# Backplane.net
KiCad netlist of a schematic drawn in EAGLE
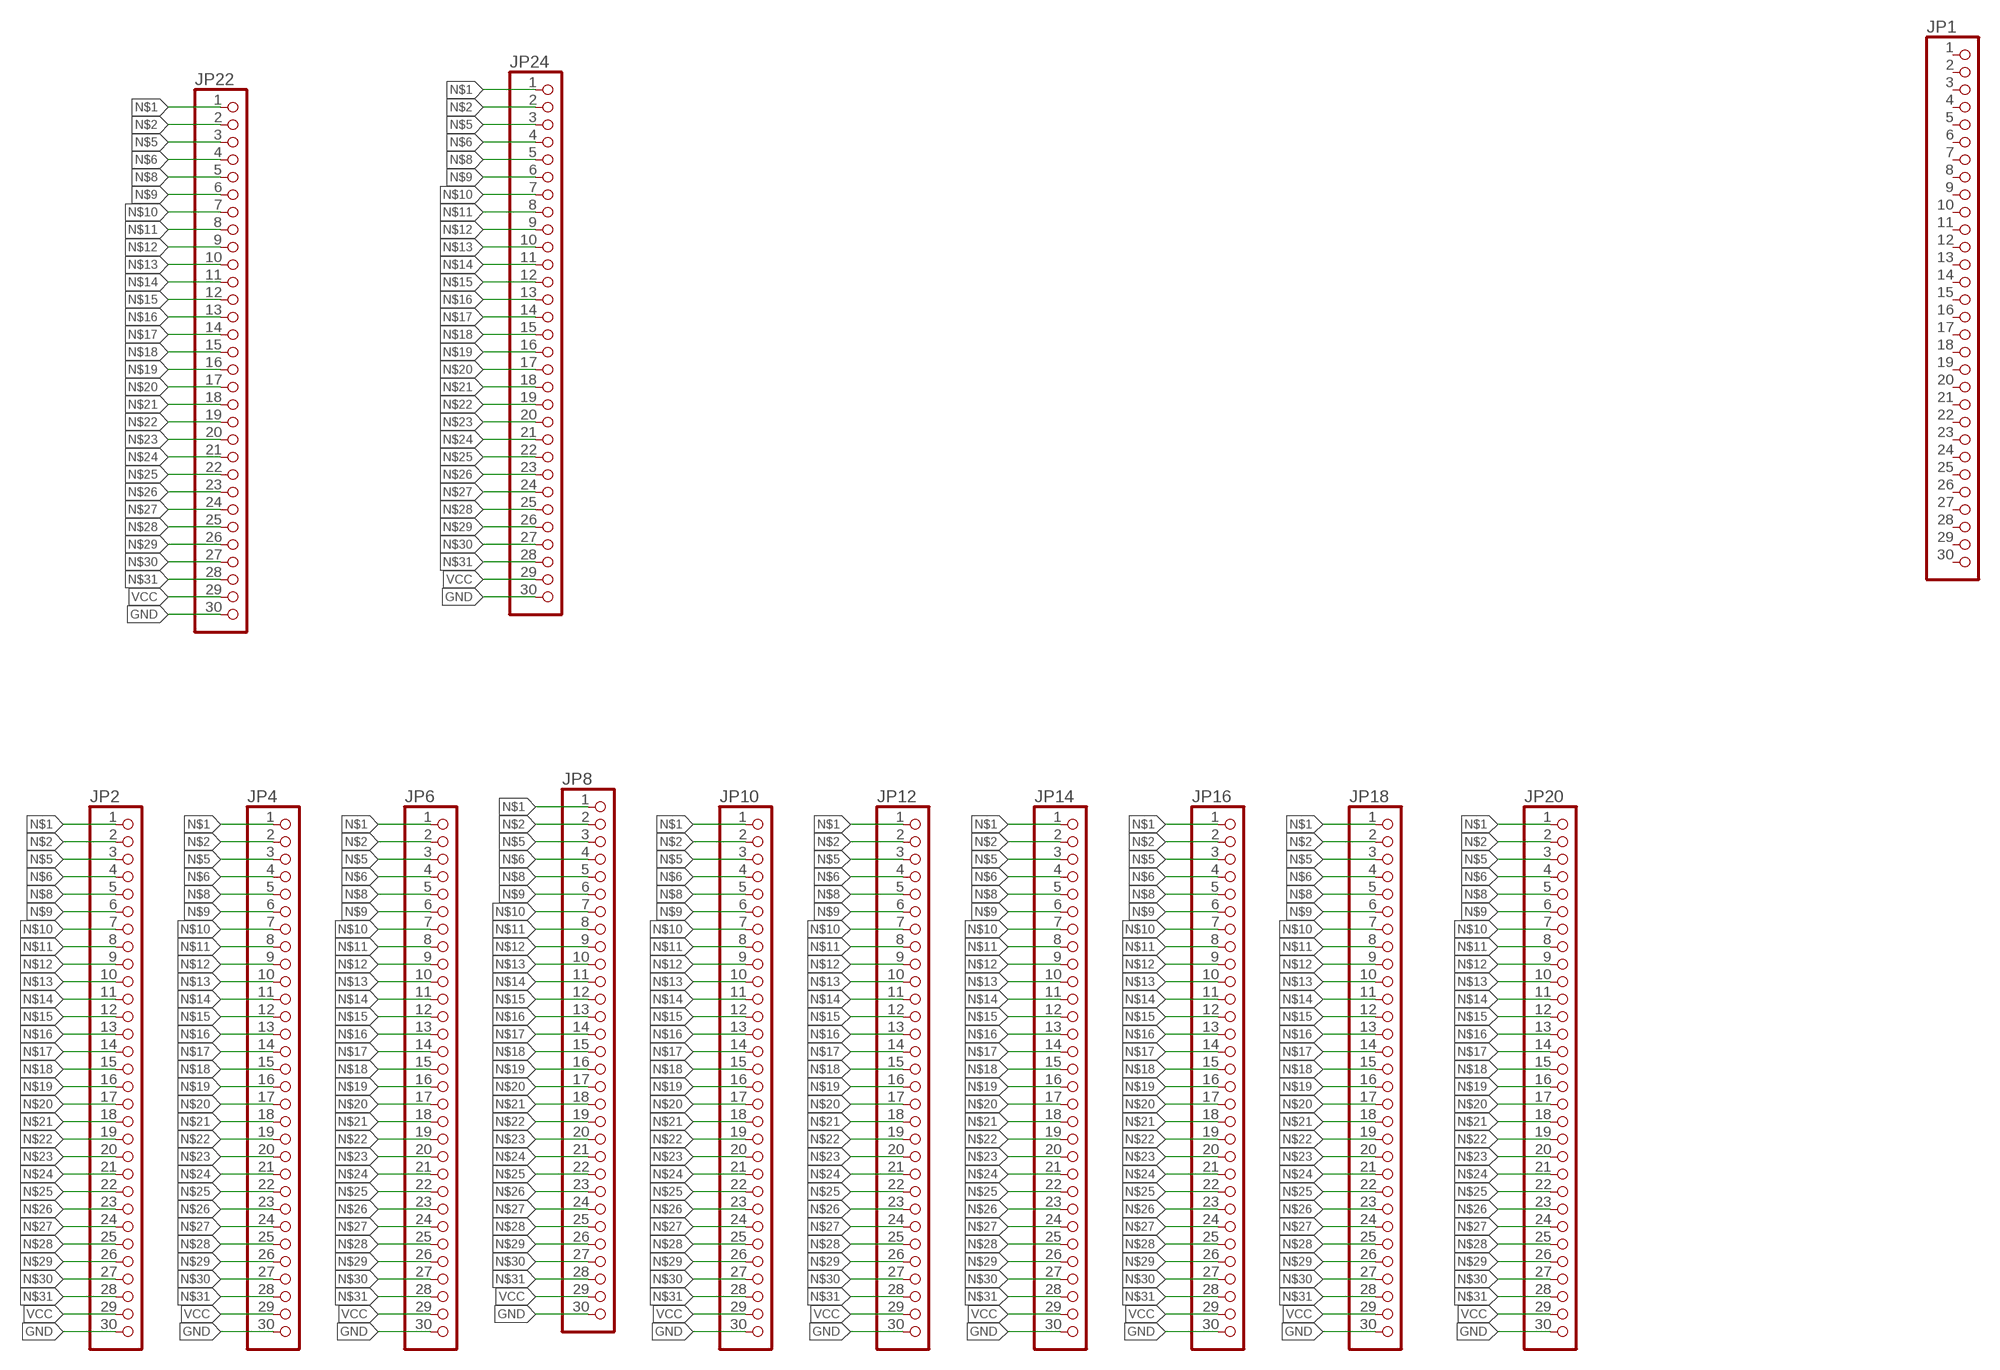
[diagram p0: schematic, sheet 1]

(export (version "E")
  (design (tool "Eeschema 10.0.6"))
  (components
    (comp (ref "JP1")
      (value "PINHD-1X30")
      (footprint "eagle-import:1X30")
      (libsource (lib "eagle-import") (part "PINHD-1X30"))
    )
    (comp (ref "JP2")
      (value "PINHD-1X30")
      (footprint "eagle-import:1X30")
      (libsource (lib "eagle-import") (part "PINHD-1X30"))
    )
    (comp (ref "JP4")
      (value "PINHD-1X30")
      (footprint "eagle-import:1X30")
      (libsource (lib "eagle-import") (part "PINHD-1X30"))
    )
    (comp (ref "JP6")
      (value "PINHD-1X30")
      (footprint "eagle-import:1X30")
      (libsource (lib "eagle-import") (part "PINHD-1X30"))
    )
    (comp (ref "JP8")
      (value "PINHD-1X30")
      (footprint "eagle-import:1X30")
      (libsource (lib "eagle-import") (part "PINHD-1X30"))
    )
    (comp (ref "JP10")
      (value "PINHD-1X30")
      (footprint "eagle-import:1X30")
      (libsource (lib "eagle-import") (part "PINHD-1X30"))
    )
    (comp (ref "JP12")
      (value "PINHD-1X30")
      (footprint "eagle-import:1X30")
      (libsource (lib "eagle-import") (part "PINHD-1X30"))
    )
    (comp (ref "JP14")
      (value "PINHD-1X30")
      (footprint "eagle-import:1X30")
      (libsource (lib "eagle-import") (part "PINHD-1X30"))
    )
    (comp (ref "JP16")
      (value "PINHD-1X30")
      (footprint "eagle-import:1X30")
      (libsource (lib "eagle-import") (part "PINHD-1X30"))
    )
    (comp (ref "JP18")
      (value "PINHD-1X30")
      (footprint "eagle-import:1X30")
      (libsource (lib "eagle-import") (part "PINHD-1X30"))
    )
    (comp (ref "JP20")
      (value "PINHD-1X30")
      (footprint "eagle-import:1X30")
      (libsource (lib "eagle-import") (part "PINHD-1X30"))
    )
    (comp (ref "JP22")
      (value "PINHD-1X30")
      (footprint "eagle-import:1X30")
      (libsource (lib "eagle-import") (part "PINHD-1X30"))
    )
    (comp (ref "JP24")
      (value "PINHD-1X30")
      (footprint "eagle-import:1X30")
      (libsource (lib "eagle-import") (part "PINHD-1X30"))
    )
  )
  (nets
    (net (code "1") (name "GND") (class "Default")
      (node (ref "JP10") (pin "30") (pinfunction "30_30") (pintype "passive"))
      (node (ref "JP12") (pin "30") (pinfunction "30_30") (pintype "passive"))
      (node (ref "JP14") (pin "30") (pinfunction "30_30") (pintype "passive"))
      (node (ref "JP16") (pin "30") (pinfunction "30_30") (pintype "passive"))
      (node (ref "JP18") (pin "30") (pinfunction "30_30") (pintype "passive"))
      (node (ref "JP2") (pin "30") (pinfunction "30_30") (pintype "passive"))
      (node (ref "JP20") (pin "30") (pinfunction "30_30") (pintype "passive"))
      (node (ref "JP22") (pin "30") (pinfunction "30_30") (pintype "passive"))
      (node (ref "JP24") (pin "30") (pinfunction "30_30") (pintype "passive"))
      (node (ref "JP4") (pin "30") (pinfunction "30_30") (pintype "passive"))
      (node (ref "JP6") (pin "30") (pinfunction "30_30") (pintype "passive"))
      (node (ref "JP8") (pin "30") (pinfunction "30_30") (pintype "passive"))
    )
    (net (code "2") (name "N$1") (class "Default")
      (node (ref "JP10") (pin "1") (pinfunction "1_1") (pintype "passive"))
      (node (ref "JP12") (pin "1") (pinfunction "1_1") (pintype "passive"))
      (node (ref "JP14") (pin "1") (pinfunction "1_1") (pintype "passive"))
      (node (ref "JP16") (pin "1") (pinfunction "1_1") (pintype "passive"))
      (node (ref "JP18") (pin "1") (pinfunction "1_1") (pintype "passive"))
      (node (ref "JP2") (pin "1") (pinfunction "1_1") (pintype "passive"))
      (node (ref "JP20") (pin "1") (pinfunction "1_1") (pintype "passive"))
      (node (ref "JP22") (pin "1") (pinfunction "1_1") (pintype "passive"))
      (node (ref "JP24") (pin "1") (pinfunction "1_1") (pintype "passive"))
      (node (ref "JP4") (pin "1") (pinfunction "1_1") (pintype "passive"))
      (node (ref "JP6") (pin "1") (pinfunction "1_1") (pintype "passive"))
      (node (ref "JP8") (pin "1") (pinfunction "1_1") (pintype "passive"))
    )
    (net (code "3") (name "N$2") (class "Default")
      (node (ref "JP10") (pin "2") (pinfunction "2_2") (pintype "passive"))
      (node (ref "JP12") (pin "2") (pinfunction "2_2") (pintype "passive"))
      (node (ref "JP14") (pin "2") (pinfunction "2_2") (pintype "passive"))
      (node (ref "JP16") (pin "2") (pinfunction "2_2") (pintype "passive"))
      (node (ref "JP18") (pin "2") (pinfunction "2_2") (pintype "passive"))
      (node (ref "JP2") (pin "2") (pinfunction "2_2") (pintype "passive"))
      (node (ref "JP20") (pin "2") (pinfunction "2_2") (pintype "passive"))
      (node (ref "JP22") (pin "2") (pinfunction "2_2") (pintype "passive"))
      (node (ref "JP24") (pin "2") (pinfunction "2_2") (pintype "passive"))
      (node (ref "JP4") (pin "2") (pinfunction "2_2") (pintype "passive"))
      (node (ref "JP6") (pin "2") (pinfunction "2_2") (pintype "passive"))
      (node (ref "JP8") (pin "2") (pinfunction "2_2") (pintype "passive"))
    )
    (net (code "4") (name "N$5") (class "Default")
      (node (ref "JP10") (pin "3") (pinfunction "3_3") (pintype "passive"))
      (node (ref "JP12") (pin "3") (pinfunction "3_3") (pintype "passive"))
      (node (ref "JP14") (pin "3") (pinfunction "3_3") (pintype "passive"))
      (node (ref "JP16") (pin "3") (pinfunction "3_3") (pintype "passive"))
      (node (ref "JP18") (pin "3") (pinfunction "3_3") (pintype "passive"))
      (node (ref "JP2") (pin "3") (pinfunction "3_3") (pintype "passive"))
      (node (ref "JP20") (pin "3") (pinfunction "3_3") (pintype "passive"))
      (node (ref "JP22") (pin "3") (pinfunction "3_3") (pintype "passive"))
      (node (ref "JP24") (pin "3") (pinfunction "3_3") (pintype "passive"))
      (node (ref "JP4") (pin "3") (pinfunction "3_3") (pintype "passive"))
      (node (ref "JP6") (pin "3") (pinfunction "3_3") (pintype "passive"))
      (node (ref "JP8") (pin "3") (pinfunction "3_3") (pintype "passive"))
    )
    (net (code "5") (name "N$6") (class "Default")
      (node (ref "JP10") (pin "4") (pinfunction "4_4") (pintype "passive"))
      (node (ref "JP12") (pin "4") (pinfunction "4_4") (pintype "passive"))
      (node (ref "JP14") (pin "4") (pinfunction "4_4") (pintype "passive"))
      (node (ref "JP16") (pin "4") (pinfunction "4_4") (pintype "passive"))
      (node (ref "JP18") (pin "4") (pinfunction "4_4") (pintype "passive"))
      (node (ref "JP2") (pin "4") (pinfunction "4_4") (pintype "passive"))
      (node (ref "JP20") (pin "4") (pinfunction "4_4") (pintype "passive"))
      (node (ref "JP22") (pin "4") (pinfunction "4_4") (pintype "passive"))
      (node (ref "JP24") (pin "4") (pinfunction "4_4") (pintype "passive"))
      (node (ref "JP4") (pin "4") (pinfunction "4_4") (pintype "passive"))
      (node (ref "JP6") (pin "4") (pinfunction "4_4") (pintype "passive"))
      (node (ref "JP8") (pin "4") (pinfunction "4_4") (pintype "passive"))
    )
    (net (code "6") (name "N$8") (class "Default")
      (node (ref "JP10") (pin "5") (pinfunction "5_5") (pintype "passive"))
      (node (ref "JP12") (pin "5") (pinfunction "5_5") (pintype "passive"))
      (node (ref "JP14") (pin "5") (pinfunction "5_5") (pintype "passive"))
      (node (ref "JP16") (pin "5") (pinfunction "5_5") (pintype "passive"))
      (node (ref "JP18") (pin "5") (pinfunction "5_5") (pintype "passive"))
      (node (ref "JP2") (pin "5") (pinfunction "5_5") (pintype "passive"))
      (node (ref "JP20") (pin "5") (pinfunction "5_5") (pintype "passive"))
      (node (ref "JP22") (pin "5") (pinfunction "5_5") (pintype "passive"))
      (node (ref "JP24") (pin "5") (pinfunction "5_5") (pintype "passive"))
      (node (ref "JP4") (pin "5") (pinfunction "5_5") (pintype "passive"))
      (node (ref "JP6") (pin "5") (pinfunction "5_5") (pintype "passive"))
      (node (ref "JP8") (pin "5") (pinfunction "5_5") (pintype "passive"))
    )
    (net (code "7") (name "N$9") (class "Default")
      (node (ref "JP10") (pin "6") (pinfunction "6_6") (pintype "passive"))
      (node (ref "JP12") (pin "6") (pinfunction "6_6") (pintype "passive"))
      (node (ref "JP14") (pin "6") (pinfunction "6_6") (pintype "passive"))
      (node (ref "JP16") (pin "6") (pinfunction "6_6") (pintype "passive"))
      (node (ref "JP18") (pin "6") (pinfunction "6_6") (pintype "passive"))
      (node (ref "JP2") (pin "6") (pinfunction "6_6") (pintype "passive"))
      (node (ref "JP20") (pin "6") (pinfunction "6_6") (pintype "passive"))
      (node (ref "JP22") (pin "6") (pinfunction "6_6") (pintype "passive"))
      (node (ref "JP24") (pin "6") (pinfunction "6_6") (pintype "passive"))
      (node (ref "JP4") (pin "6") (pinfunction "6_6") (pintype "passive"))
      (node (ref "JP6") (pin "6") (pinfunction "6_6") (pintype "passive"))
      (node (ref "JP8") (pin "6") (pinfunction "6_6") (pintype "passive"))
    )
    (net (code "8") (name "N$10") (class "Default")
      (node (ref "JP10") (pin "7") (pinfunction "7_7") (pintype "passive"))
      (node (ref "JP12") (pin "7") (pinfunction "7_7") (pintype "passive"))
      (node (ref "JP14") (pin "7") (pinfunction "7_7") (pintype "passive"))
      (node (ref "JP16") (pin "7") (pinfunction "7_7") (pintype "passive"))
      (node (ref "JP18") (pin "7") (pinfunction "7_7") (pintype "passive"))
      (node (ref "JP2") (pin "7") (pinfunction "7_7") (pintype "passive"))
      (node (ref "JP20") (pin "7") (pinfunction "7_7") (pintype "passive"))
      (node (ref "JP22") (pin "7") (pinfunction "7_7") (pintype "passive"))
      (node (ref "JP24") (pin "7") (pinfunction "7_7") (pintype "passive"))
      (node (ref "JP4") (pin "7") (pinfunction "7_7") (pintype "passive"))
      (node (ref "JP6") (pin "7") (pinfunction "7_7") (pintype "passive"))
      (node (ref "JP8") (pin "7") (pinfunction "7_7") (pintype "passive"))
    )
    (net (code "9") (name "N$11") (class "Default")
      (node (ref "JP10") (pin "8") (pinfunction "8_8") (pintype "passive"))
      (node (ref "JP12") (pin "8") (pinfunction "8_8") (pintype "passive"))
      (node (ref "JP14") (pin "8") (pinfunction "8_8") (pintype "passive"))
      (node (ref "JP16") (pin "8") (pinfunction "8_8") (pintype "passive"))
      (node (ref "JP18") (pin "8") (pinfunction "8_8") (pintype "passive"))
      (node (ref "JP2") (pin "8") (pinfunction "8_8") (pintype "passive"))
      (node (ref "JP20") (pin "8") (pinfunction "8_8") (pintype "passive"))
      (node (ref "JP22") (pin "8") (pinfunction "8_8") (pintype "passive"))
      (node (ref "JP24") (pin "8") (pinfunction "8_8") (pintype "passive"))
      (node (ref "JP4") (pin "8") (pinfunction "8_8") (pintype "passive"))
      (node (ref "JP6") (pin "8") (pinfunction "8_8") (pintype "passive"))
      (node (ref "JP8") (pin "8") (pinfunction "8_8") (pintype "passive"))
    )
    (net (code "10") (name "N$12") (class "Default")
      (node (ref "JP10") (pin "9") (pinfunction "9_9") (pintype "passive"))
      (node (ref "JP12") (pin "9") (pinfunction "9_9") (pintype "passive"))
      (node (ref "JP14") (pin "9") (pinfunction "9_9") (pintype "passive"))
      (node (ref "JP16") (pin "9") (pinfunction "9_9") (pintype "passive"))
      (node (ref "JP18") (pin "9") (pinfunction "9_9") (pintype "passive"))
      (node (ref "JP2") (pin "9") (pinfunction "9_9") (pintype "passive"))
      (node (ref "JP20") (pin "9") (pinfunction "9_9") (pintype "passive"))
      (node (ref "JP22") (pin "9") (pinfunction "9_9") (pintype "passive"))
      (node (ref "JP24") (pin "9") (pinfunction "9_9") (pintype "passive"))
      (node (ref "JP4") (pin "9") (pinfunction "9_9") (pintype "passive"))
      (node (ref "JP6") (pin "9") (pinfunction "9_9") (pintype "passive"))
      (node (ref "JP8") (pin "9") (pinfunction "9_9") (pintype "passive"))
    )
    (net (code "11") (name "N$13") (class "Default")
      (node (ref "JP10") (pin "10") (pinfunction "10_10") (pintype "passive"))
      (node (ref "JP12") (pin "10") (pinfunction "10_10") (pintype "passive"))
      (node (ref "JP14") (pin "10") (pinfunction "10_10") (pintype "passive"))
      (node (ref "JP16") (pin "10") (pinfunction "10_10") (pintype "passive"))
      (node (ref "JP18") (pin "10") (pinfunction "10_10") (pintype "passive"))
      (node (ref "JP2") (pin "10") (pinfunction "10_10") (pintype "passive"))
      (node (ref "JP20") (pin "10") (pinfunction "10_10") (pintype "passive"))
      (node (ref "JP22") (pin "10") (pinfunction "10_10") (pintype "passive"))
      (node (ref "JP24") (pin "10") (pinfunction "10_10") (pintype "passive"))
      (node (ref "JP4") (pin "10") (pinfunction "10_10") (pintype "passive"))
      (node (ref "JP6") (pin "10") (pinfunction "10_10") (pintype "passive"))
      (node (ref "JP8") (pin "10") (pinfunction "10_10") (pintype "passive"))
    )
    (net (code "12") (name "N$14") (class "Default")
      (node (ref "JP10") (pin "11") (pinfunction "11_11") (pintype "passive"))
      (node (ref "JP12") (pin "11") (pinfunction "11_11") (pintype "passive"))
      (node (ref "JP14") (pin "11") (pinfunction "11_11") (pintype "passive"))
      (node (ref "JP16") (pin "11") (pinfunction "11_11") (pintype "passive"))
      (node (ref "JP18") (pin "11") (pinfunction "11_11") (pintype "passive"))
      (node (ref "JP2") (pin "11") (pinfunction "11_11") (pintype "passive"))
      (node (ref "JP20") (pin "11") (pinfunction "11_11") (pintype "passive"))
      (node (ref "JP22") (pin "11") (pinfunction "11_11") (pintype "passive"))
      (node (ref "JP24") (pin "11") (pinfunction "11_11") (pintype "passive"))
      (node (ref "JP4") (pin "11") (pinfunction "11_11") (pintype "passive"))
      (node (ref "JP6") (pin "11") (pinfunction "11_11") (pintype "passive"))
      (node (ref "JP8") (pin "11") (pinfunction "11_11") (pintype "passive"))
    )
    (net (code "13") (name "N$15") (class "Default")
      (node (ref "JP10") (pin "12") (pinfunction "12_12") (pintype "passive"))
      (node (ref "JP12") (pin "12") (pinfunction "12_12") (pintype "passive"))
      (node (ref "JP14") (pin "12") (pinfunction "12_12") (pintype "passive"))
      (node (ref "JP16") (pin "12") (pinfunction "12_12") (pintype "passive"))
      (node (ref "JP18") (pin "12") (pinfunction "12_12") (pintype "passive"))
      (node (ref "JP2") (pin "12") (pinfunction "12_12") (pintype "passive"))
      (node (ref "JP20") (pin "12") (pinfunction "12_12") (pintype "passive"))
      (node (ref "JP22") (pin "12") (pinfunction "12_12") (pintype "passive"))
      (node (ref "JP24") (pin "12") (pinfunction "12_12") (pintype "passive"))
      (node (ref "JP4") (pin "12") (pinfunction "12_12") (pintype "passive"))
      (node (ref "JP6") (pin "12") (pinfunction "12_12") (pintype "passive"))
      (node (ref "JP8") (pin "12") (pinfunction "12_12") (pintype "passive"))
    )
    (net (code "14") (name "N$16") (class "Default")
      (node (ref "JP10") (pin "13") (pinfunction "13_13") (pintype "passive"))
      (node (ref "JP12") (pin "13") (pinfunction "13_13") (pintype "passive"))
      (node (ref "JP14") (pin "13") (pinfunction "13_13") (pintype "passive"))
      (node (ref "JP16") (pin "13") (pinfunction "13_13") (pintype "passive"))
      (node (ref "JP18") (pin "13") (pinfunction "13_13") (pintype "passive"))
      (node (ref "JP2") (pin "13") (pinfunction "13_13") (pintype "passive"))
      (node (ref "JP20") (pin "13") (pinfunction "13_13") (pintype "passive"))
      (node (ref "JP22") (pin "13") (pinfunction "13_13") (pintype "passive"))
      (node (ref "JP24") (pin "13") (pinfunction "13_13") (pintype "passive"))
      (node (ref "JP4") (pin "13") (pinfunction "13_13") (pintype "passive"))
      (node (ref "JP6") (pin "13") (pinfunction "13_13") (pintype "passive"))
      (node (ref "JP8") (pin "13") (pinfunction "13_13") (pintype "passive"))
    )
    (net (code "15") (name "N$17") (class "Default")
      (node (ref "JP10") (pin "14") (pinfunction "14_14") (pintype "passive"))
      (node (ref "JP12") (pin "14") (pinfunction "14_14") (pintype "passive"))
      (node (ref "JP14") (pin "14") (pinfunction "14_14") (pintype "passive"))
      (node (ref "JP16") (pin "14") (pinfunction "14_14") (pintype "passive"))
      (node (ref "JP18") (pin "14") (pinfunction "14_14") (pintype "passive"))
      (node (ref "JP2") (pin "14") (pinfunction "14_14") (pintype "passive"))
      (node (ref "JP20") (pin "14") (pinfunction "14_14") (pintype "passive"))
      (node (ref "JP22") (pin "14") (pinfunction "14_14") (pintype "passive"))
      (node (ref "JP24") (pin "14") (pinfunction "14_14") (pintype "passive"))
      (node (ref "JP4") (pin "14") (pinfunction "14_14") (pintype "passive"))
      (node (ref "JP6") (pin "14") (pinfunction "14_14") (pintype "passive"))
      (node (ref "JP8") (pin "14") (pinfunction "14_14") (pintype "passive"))
    )
    (net (code "16") (name "N$18") (class "Default")
      (node (ref "JP10") (pin "15") (pinfunction "15_15") (pintype "passive"))
      (node (ref "JP12") (pin "15") (pinfunction "15_15") (pintype "passive"))
      (node (ref "JP14") (pin "15") (pinfunction "15_15") (pintype "passive"))
      (node (ref "JP16") (pin "15") (pinfunction "15_15") (pintype "passive"))
      (node (ref "JP18") (pin "15") (pinfunction "15_15") (pintype "passive"))
      (node (ref "JP2") (pin "15") (pinfunction "15_15") (pintype "passive"))
      (node (ref "JP20") (pin "15") (pinfunction "15_15") (pintype "passive"))
      (node (ref "JP22") (pin "15") (pinfunction "15_15") (pintype "passive"))
      (node (ref "JP24") (pin "15") (pinfunction "15_15") (pintype "passive"))
      (node (ref "JP4") (pin "15") (pinfunction "15_15") (pintype "passive"))
      (node (ref "JP6") (pin "15") (pinfunction "15_15") (pintype "passive"))
      (node (ref "JP8") (pin "15") (pinfunction "15_15") (pintype "passive"))
    )
    (net (code "17") (name "N$19") (class "Default")
      (node (ref "JP10") (pin "16") (pinfunction "16_16") (pintype "passive"))
      (node (ref "JP12") (pin "16") (pinfunction "16_16") (pintype "passive"))
      (node (ref "JP14") (pin "16") (pinfunction "16_16") (pintype "passive"))
      (node (ref "JP16") (pin "16") (pinfunction "16_16") (pintype "passive"))
      (node (ref "JP18") (pin "16") (pinfunction "16_16") (pintype "passive"))
      (node (ref "JP2") (pin "16") (pinfunction "16_16") (pintype "passive"))
      (node (ref "JP20") (pin "16") (pinfunction "16_16") (pintype "passive"))
      (node (ref "JP22") (pin "16") (pinfunction "16_16") (pintype "passive"))
      (node (ref "JP24") (pin "16") (pinfunction "16_16") (pintype "passive"))
      (node (ref "JP4") (pin "16") (pinfunction "16_16") (pintype "passive"))
      (node (ref "JP6") (pin "16") (pinfunction "16_16") (pintype "passive"))
      (node (ref "JP8") (pin "16") (pinfunction "16_16") (pintype "passive"))
    )
    (net (code "18") (name "N$20") (class "Default")
      (node (ref "JP10") (pin "17") (pinfunction "17_17") (pintype "passive"))
      (node (ref "JP12") (pin "17") (pinfunction "17_17") (pintype "passive"))
      (node (ref "JP14") (pin "17") (pinfunction "17_17") (pintype "passive"))
      (node (ref "JP16") (pin "17") (pinfunction "17_17") (pintype "passive"))
      (node (ref "JP18") (pin "17") (pinfunction "17_17") (pintype "passive"))
      (node (ref "JP2") (pin "17") (pinfunction "17_17") (pintype "passive"))
      (node (ref "JP20") (pin "17") (pinfunction "17_17") (pintype "passive"))
      (node (ref "JP22") (pin "17") (pinfunction "17_17") (pintype "passive"))
      (node (ref "JP24") (pin "17") (pinfunction "17_17") (pintype "passive"))
      (node (ref "JP4") (pin "17") (pinfunction "17_17") (pintype "passive"))
      (node (ref "JP6") (pin "17") (pinfunction "17_17") (pintype "passive"))
      (node (ref "JP8") (pin "17") (pinfunction "17_17") (pintype "passive"))
    )
    (net (code "19") (name "N$21") (class "Default")
      (node (ref "JP10") (pin "18") (pinfunction "18_18") (pintype "passive"))
      (node (ref "JP12") (pin "18") (pinfunction "18_18") (pintype "passive"))
      (node (ref "JP14") (pin "18") (pinfunction "18_18") (pintype "passive"))
      (node (ref "JP16") (pin "18") (pinfunction "18_18") (pintype "passive"))
      (node (ref "JP18") (pin "18") (pinfunction "18_18") (pintype "passive"))
      (node (ref "JP2") (pin "18") (pinfunction "18_18") (pintype "passive"))
      (node (ref "JP20") (pin "18") (pinfunction "18_18") (pintype "passive"))
      (node (ref "JP22") (pin "18") (pinfunction "18_18") (pintype "passive"))
      (node (ref "JP24") (pin "18") (pinfunction "18_18") (pintype "passive"))
      (node (ref "JP4") (pin "18") (pinfunction "18_18") (pintype "passive"))
      (node (ref "JP6") (pin "18") (pinfunction "18_18") (pintype "passive"))
      (node (ref "JP8") (pin "18") (pinfunction "18_18") (pintype "passive"))
    )
    (net (code "20") (name "N$22") (class "Default")
      (node (ref "JP10") (pin "19") (pinfunction "19_19") (pintype "passive"))
      (node (ref "JP12") (pin "19") (pinfunction "19_19") (pintype "passive"))
      (node (ref "JP14") (pin "19") (pinfunction "19_19") (pintype "passive"))
      (node (ref "JP16") (pin "19") (pinfunction "19_19") (pintype "passive"))
      (node (ref "JP18") (pin "19") (pinfunction "19_19") (pintype "passive"))
      (node (ref "JP2") (pin "19") (pinfunction "19_19") (pintype "passive"))
      (node (ref "JP20") (pin "19") (pinfunction "19_19") (pintype "passive"))
      (node (ref "JP22") (pin "19") (pinfunction "19_19") (pintype "passive"))
      (node (ref "JP24") (pin "19") (pinfunction "19_19") (pintype "passive"))
      (node (ref "JP4") (pin "19") (pinfunction "19_19") (pintype "passive"))
      (node (ref "JP6") (pin "19") (pinfunction "19_19") (pintype "passive"))
      (node (ref "JP8") (pin "19") (pinfunction "19_19") (pintype "passive"))
    )
    (net (code "21") (name "N$23") (class "Default")
      (node (ref "JP10") (pin "20") (pinfunction "20_20") (pintype "passive"))
      (node (ref "JP12") (pin "20") (pinfunction "20_20") (pintype "passive"))
      (node (ref "JP14") (pin "20") (pinfunction "20_20") (pintype "passive"))
      (node (ref "JP16") (pin "20") (pinfunction "20_20") (pintype "passive"))
      (node (ref "JP18") (pin "20") (pinfunction "20_20") (pintype "passive"))
      (node (ref "JP2") (pin "20") (pinfunction "20_20") (pintype "passive"))
      (node (ref "JP20") (pin "20") (pinfunction "20_20") (pintype "passive"))
      (node (ref "JP22") (pin "20") (pinfunction "20_20") (pintype "passive"))
      (node (ref "JP24") (pin "20") (pinfunction "20_20") (pintype "passive"))
      (node (ref "JP4") (pin "20") (pinfunction "20_20") (pintype "passive"))
      (node (ref "JP6") (pin "20") (pinfunction "20_20") (pintype "passive"))
      (node (ref "JP8") (pin "20") (pinfunction "20_20") (pintype "passive"))
    )
    (net (code "22") (name "N$24") (class "Default")
      (node (ref "JP10") (pin "21") (pinfunction "21_21") (pintype "passive"))
      (node (ref "JP12") (pin "21") (pinfunction "21_21") (pintype "passive"))
      (node (ref "JP14") (pin "21") (pinfunction "21_21") (pintype "passive"))
      (node (ref "JP16") (pin "21") (pinfunction "21_21") (pintype "passive"))
      (node (ref "JP18") (pin "21") (pinfunction "21_21") (pintype "passive"))
      (node (ref "JP2") (pin "21") (pinfunction "21_21") (pintype "passive"))
      (node (ref "JP20") (pin "21") (pinfunction "21_21") (pintype "passive"))
      (node (ref "JP22") (pin "21") (pinfunction "21_21") (pintype "passive"))
      (node (ref "JP24") (pin "21") (pinfunction "21_21") (pintype "passive"))
      (node (ref "JP4") (pin "21") (pinfunction "21_21") (pintype "passive"))
      (node (ref "JP6") (pin "21") (pinfunction "21_21") (pintype "passive"))
      (node (ref "JP8") (pin "21") (pinfunction "21_21") (pintype "passive"))
    )
    (net (code "23") (name "N$25") (class "Default")
      (node (ref "JP10") (pin "22") (pinfunction "22_22") (pintype "passive"))
      (node (ref "JP12") (pin "22") (pinfunction "22_22") (pintype "passive"))
      (node (ref "JP14") (pin "22") (pinfunction "22_22") (pintype "passive"))
      (node (ref "JP16") (pin "22") (pinfunction "22_22") (pintype "passive"))
      (node (ref "JP18") (pin "22") (pinfunction "22_22") (pintype "passive"))
      (node (ref "JP2") (pin "22") (pinfunction "22_22") (pintype "passive"))
      (node (ref "JP20") (pin "22") (pinfunction "22_22") (pintype "passive"))
      (node (ref "JP22") (pin "22") (pinfunction "22_22") (pintype "passive"))
      (node (ref "JP24") (pin "22") (pinfunction "22_22") (pintype "passive"))
      (node (ref "JP4") (pin "22") (pinfunction "22_22") (pintype "passive"))
      (node (ref "JP6") (pin "22") (pinfunction "22_22") (pintype "passive"))
      (node (ref "JP8") (pin "22") (pinfunction "22_22") (pintype "passive"))
    )
    (net (code "24") (name "N$26") (class "Default")
      (node (ref "JP10") (pin "23") (pinfunction "23_23") (pintype "passive"))
      (node (ref "JP12") (pin "23") (pinfunction "23_23") (pintype "passive"))
      (node (ref "JP14") (pin "23") (pinfunction "23_23") (pintype "passive"))
      (node (ref "JP16") (pin "23") (pinfunction "23_23") (pintype "passive"))
      (node (ref "JP18") (pin "23") (pinfunction "23_23") (pintype "passive"))
      (node (ref "JP2") (pin "23") (pinfunction "23_23") (pintype "passive"))
      (node (ref "JP20") (pin "23") (pinfunction "23_23") (pintype "passive"))
      (node (ref "JP22") (pin "23") (pinfunction "23_23") (pintype "passive"))
      (node (ref "JP24") (pin "23") (pinfunction "23_23") (pintype "passive"))
      (node (ref "JP4") (pin "23") (pinfunction "23_23") (pintype "passive"))
      (node (ref "JP6") (pin "23") (pinfunction "23_23") (pintype "passive"))
      (node (ref "JP8") (pin "23") (pinfunction "23_23") (pintype "passive"))
    )
    (net (code "25") (name "N$27") (class "Default")
      (node (ref "JP10") (pin "24") (pinfunction "24_24") (pintype "passive"))
      (node (ref "JP12") (pin "24") (pinfunction "24_24") (pintype "passive"))
      (node (ref "JP14") (pin "24") (pinfunction "24_24") (pintype "passive"))
      (node (ref "JP16") (pin "24") (pinfunction "24_24") (pintype "passive"))
      (node (ref "JP18") (pin "24") (pinfunction "24_24") (pintype "passive"))
      (node (ref "JP2") (pin "24") (pinfunction "24_24") (pintype "passive"))
      (node (ref "JP20") (pin "24") (pinfunction "24_24") (pintype "passive"))
      (node (ref "JP22") (pin "24") (pinfunction "24_24") (pintype "passive"))
      (node (ref "JP24") (pin "24") (pinfunction "24_24") (pintype "passive"))
      (node (ref "JP4") (pin "24") (pinfunction "24_24") (pintype "passive"))
      (node (ref "JP6") (pin "24") (pinfunction "24_24") (pintype "passive"))
      (node (ref "JP8") (pin "24") (pinfunction "24_24") (pintype "passive"))
    )
    (net (code "26") (name "N$28") (class "Default")
      (node (ref "JP10") (pin "25") (pinfunction "25_25") (pintype "passive"))
      (node (ref "JP12") (pin "25") (pinfunction "25_25") (pintype "passive"))
      (node (ref "JP14") (pin "25") (pinfunction "25_25") (pintype "passive"))
      (node (ref "JP16") (pin "25") (pinfunction "25_25") (pintype "passive"))
      (node (ref "JP18") (pin "25") (pinfunction "25_25") (pintype "passive"))
      (node (ref "JP2") (pin "25") (pinfunction "25_25") (pintype "passive"))
      (node (ref "JP20") (pin "25") (pinfunction "25_25") (pintype "passive"))
      (node (ref "JP22") (pin "25") (pinfunction "25_25") (pintype "passive"))
      (node (ref "JP24") (pin "25") (pinfunction "25_25") (pintype "passive"))
      (node (ref "JP4") (pin "25") (pinfunction "25_25") (pintype "passive"))
      (node (ref "JP6") (pin "25") (pinfunction "25_25") (pintype "passive"))
      (node (ref "JP8") (pin "25") (pinfunction "25_25") (pintype "passive"))
    )
    (net (code "27") (name "N$29") (class "Default")
      (node (ref "JP10") (pin "26") (pinfunction "26_26") (pintype "passive"))
      (node (ref "JP12") (pin "26") (pinfunction "26_26") (pintype "passive"))
      (node (ref "JP14") (pin "26") (pinfunction "26_26") (pintype "passive"))
      (node (ref "JP16") (pin "26") (pinfunction "26_26") (pintype "passive"))
      (node (ref "JP18") (pin "26") (pinfunction "26_26") (pintype "passive"))
      (node (ref "JP2") (pin "26") (pinfunction "26_26") (pintype "passive"))
      (node (ref "JP20") (pin "26") (pinfunction "26_26") (pintype "passive"))
      (node (ref "JP22") (pin "26") (pinfunction "26_26") (pintype "passive"))
      (node (ref "JP24") (pin "26") (pinfunction "26_26") (pintype "passive"))
      (node (ref "JP4") (pin "26") (pinfunction "26_26") (pintype "passive"))
      (node (ref "JP6") (pin "26") (pinfunction "26_26") (pintype "passive"))
      (node (ref "JP8") (pin "26") (pinfunction "26_26") (pintype "passive"))
    )
    (net (code "28") (name "N$30") (class "Default")
      (node (ref "JP10") (pin "27") (pinfunction "27_27") (pintype "passive"))
      (node (ref "JP12") (pin "27") (pinfunction "27_27") (pintype "passive"))
      (node (ref "JP14") (pin "27") (pinfunction "27_27") (pintype "passive"))
      (node (ref "JP16") (pin "27") (pinfunction "27_27") (pintype "passive"))
      (node (ref "JP18") (pin "27") (pinfunction "27_27") (pintype "passive"))
      (node (ref "JP2") (pin "27") (pinfunction "27_27") (pintype "passive"))
      (node (ref "JP20") (pin "27") (pinfunction "27_27") (pintype "passive"))
      (node (ref "JP22") (pin "27") (pinfunction "27_27") (pintype "passive"))
      (node (ref "JP24") (pin "27") (pinfunction "27_27") (pintype "passive"))
      (node (ref "JP4") (pin "27") (pinfunction "27_27") (pintype "passive"))
      (node (ref "JP6") (pin "27") (pinfunction "27_27") (pintype "passive"))
      (node (ref "JP8") (pin "27") (pinfunction "27_27") (pintype "passive"))
    )
    (net (code "29") (name "N$31") (class "Default")
      (node (ref "JP10") (pin "28") (pinfunction "28_28") (pintype "passive"))
      (node (ref "JP12") (pin "28") (pinfunction "28_28") (pintype "passive"))
      (node (ref "JP14") (pin "28") (pinfunction "28_28") (pintype "passive"))
      (node (ref "JP16") (pin "28") (pinfunction "28_28") (pintype "passive"))
      (node (ref "JP18") (pin "28") (pinfunction "28_28") (pintype "passive"))
      (node (ref "JP2") (pin "28") (pinfunction "28_28") (pintype "passive"))
      (node (ref "JP20") (pin "28") (pinfunction "28_28") (pintype "passive"))
      (node (ref "JP22") (pin "28") (pinfunction "28_28") (pintype "passive"))
      (node (ref "JP24") (pin "28") (pinfunction "28_28") (pintype "passive"))
      (node (ref "JP4") (pin "28") (pinfunction "28_28") (pintype "passive"))
      (node (ref "JP6") (pin "28") (pinfunction "28_28") (pintype "passive"))
      (node (ref "JP8") (pin "28") (pinfunction "28_28") (pintype "passive"))
    )
    (net (code "30") (name "VCC") (class "Default")
      (node (ref "JP10") (pin "29") (pinfunction "29_29") (pintype "passive"))
      (node (ref "JP12") (pin "29") (pinfunction "29_29") (pintype "passive"))
      (node (ref "JP14") (pin "29") (pinfunction "29_29") (pintype "passive"))
      (node (ref "JP16") (pin "29") (pinfunction "29_29") (pintype "passive"))
      (node (ref "JP18") (pin "29") (pinfunction "29_29") (pintype "passive"))
      (node (ref "JP2") (pin "29") (pinfunction "29_29") (pintype "passive"))
      (node (ref "JP20") (pin "29") (pinfunction "29_29") (pintype "passive"))
      (node (ref "JP22") (pin "29") (pinfunction "29_29") (pintype "passive"))
      (node (ref "JP24") (pin "29") (pinfunction "29_29") (pintype "passive"))
      (node (ref "JP4") (pin "29") (pinfunction "29_29") (pintype "passive"))
      (node (ref "JP6") (pin "29") (pinfunction "29_29") (pintype "passive"))
      (node (ref "JP8") (pin "29") (pinfunction "29_29") (pintype "passive"))
    )
    (net (code "31") (name "unconnected-(JP1-Pad1)") (class "Default")
      (node (ref "JP1") (pin "1") (pinfunction "1_1") (pintype "passive"))
    )
    (net (code "32") (name "unconnected-(JP1-Pad2)") (class "Default")
      (node (ref "JP1") (pin "2") (pinfunction "2_2") (pintype "passive"))
    )
    (net (code "33") (name "unconnected-(JP1-Pad3)") (class "Default")
      (node (ref "JP1") (pin "3") (pinfunction "3_3") (pintype "passive"))
    )
    (net (code "34") (name "unconnected-(JP1-Pad4)") (class "Default")
      (node (ref "JP1") (pin "4") (pinfunction "4_4") (pintype "passive"))
    )
    (net (code "35") (name "unconnected-(JP1-Pad5)") (class "Default")
      (node (ref "JP1") (pin "5") (pinfunction "5_5") (pintype "passive"))
    )
    (net (code "36") (name "unconnected-(JP1-Pad6)") (class "Default")
      (node (ref "JP1") (pin "6") (pinfunction "6_6") (pintype "passive"))
    )
    (net (code "37") (name "unconnected-(JP1-Pad7)") (class "Default")
      (node (ref "JP1") (pin "7") (pinfunction "7_7") (pintype "passive"))
    )
    (net (code "38") (name "unconnected-(JP1-Pad8)") (class "Default")
      (node (ref "JP1") (pin "8") (pinfunction "8_8") (pintype "passive"))
    )
    (net (code "39") (name "unconnected-(JP1-Pad9)") (class "Default")
      (node (ref "JP1") (pin "9") (pinfunction "9_9") (pintype "passive"))
    )
    (net (code "40") (name "unconnected-(JP1-Pad10)") (class "Default")
      (node (ref "JP1") (pin "10") (pinfunction "10_10") (pintype "passive"))
    )
    (net (code "41") (name "unconnected-(JP1-Pad11)") (class "Default")
      (node (ref "JP1") (pin "11") (pinfunction "11_11") (pintype "passive"))
    )
    (net (code "42") (name "unconnected-(JP1-Pad12)") (class "Default")
      (node (ref "JP1") (pin "12") (pinfunction "12_12") (pintype "passive"))
    )
    (net (code "43") (name "unconnected-(JP1-Pad13)") (class "Default")
      (node (ref "JP1") (pin "13") (pinfunction "13_13") (pintype "passive"))
    )
    (net (code "44") (name "unconnected-(JP1-Pad14)") (class "Default")
      (node (ref "JP1") (pin "14") (pinfunction "14_14") (pintype "passive"))
    )
    (net (code "45") (name "unconnected-(JP1-Pad15)") (class "Default")
      (node (ref "JP1") (pin "15") (pinfunction "15_15") (pintype "passive"))
    )
    (net (code "46") (name "unconnected-(JP1-Pad16)") (class "Default")
      (node (ref "JP1") (pin "16") (pinfunction "16_16") (pintype "passive"))
    )
    (net (code "47") (name "unconnected-(JP1-Pad17)") (class "Default")
      (node (ref "JP1") (pin "17") (pinfunction "17_17") (pintype "passive"))
    )
    (net (code "48") (name "unconnected-(JP1-Pad18)") (class "Default")
      (node (ref "JP1") (pin "18") (pinfunction "18_18") (pintype "passive"))
    )
    (net (code "49") (name "unconnected-(JP1-Pad19)") (class "Default")
      (node (ref "JP1") (pin "19") (pinfunction "19_19") (pintype "passive"))
    )
    (net (code "50") (name "unconnected-(JP1-Pad20)") (class "Default")
      (node (ref "JP1") (pin "20") (pinfunction "20_20") (pintype "passive"))
    )
    (net (code "51") (name "unconnected-(JP1-Pad21)") (class "Default")
      (node (ref "JP1") (pin "21") (pinfunction "21_21") (pintype "passive"))
    )
    (net (code "52") (name "unconnected-(JP1-Pad22)") (class "Default")
      (node (ref "JP1") (pin "22") (pinfunction "22_22") (pintype "passive"))
    )
    (net (code "53") (name "unconnected-(JP1-Pad23)") (class "Default")
      (node (ref "JP1") (pin "23") (pinfunction "23_23") (pintype "passive"))
    )
    (net (code "54") (name "unconnected-(JP1-Pad24)") (class "Default")
      (node (ref "JP1") (pin "24") (pinfunction "24_24") (pintype "passive"))
    )
    (net (code "55") (name "unconnected-(JP1-Pad25)") (class "Default")
      (node (ref "JP1") (pin "25") (pinfunction "25_25") (pintype "passive"))
    )
    (net (code "56") (name "unconnected-(JP1-Pad26)") (class "Default")
      (node (ref "JP1") (pin "26") (pinfunction "26_26") (pintype "passive"))
    )
    (net (code "57") (name "unconnected-(JP1-Pad27)") (class "Default")
      (node (ref "JP1") (pin "27") (pinfunction "27_27") (pintype "passive"))
    )
    (net (code "58") (name "unconnected-(JP1-Pad28)") (class "Default")
      (node (ref "JP1") (pin "28") (pinfunction "28_28") (pintype "passive"))
    )
    (net (code "59") (name "unconnected-(JP1-Pad29)") (class "Default")
      (node (ref "JP1") (pin "29") (pinfunction "29_29") (pintype "passive"))
    )
    (net (code "60") (name "unconnected-(JP1-Pad30)") (class "Default")
      (node (ref "JP1") (pin "30") (pinfunction "30_30") (pintype "passive"))
    )
  )
)
